# FPGA_FMC.net
KiCad netlist of a schematic drawn in Altium Designer
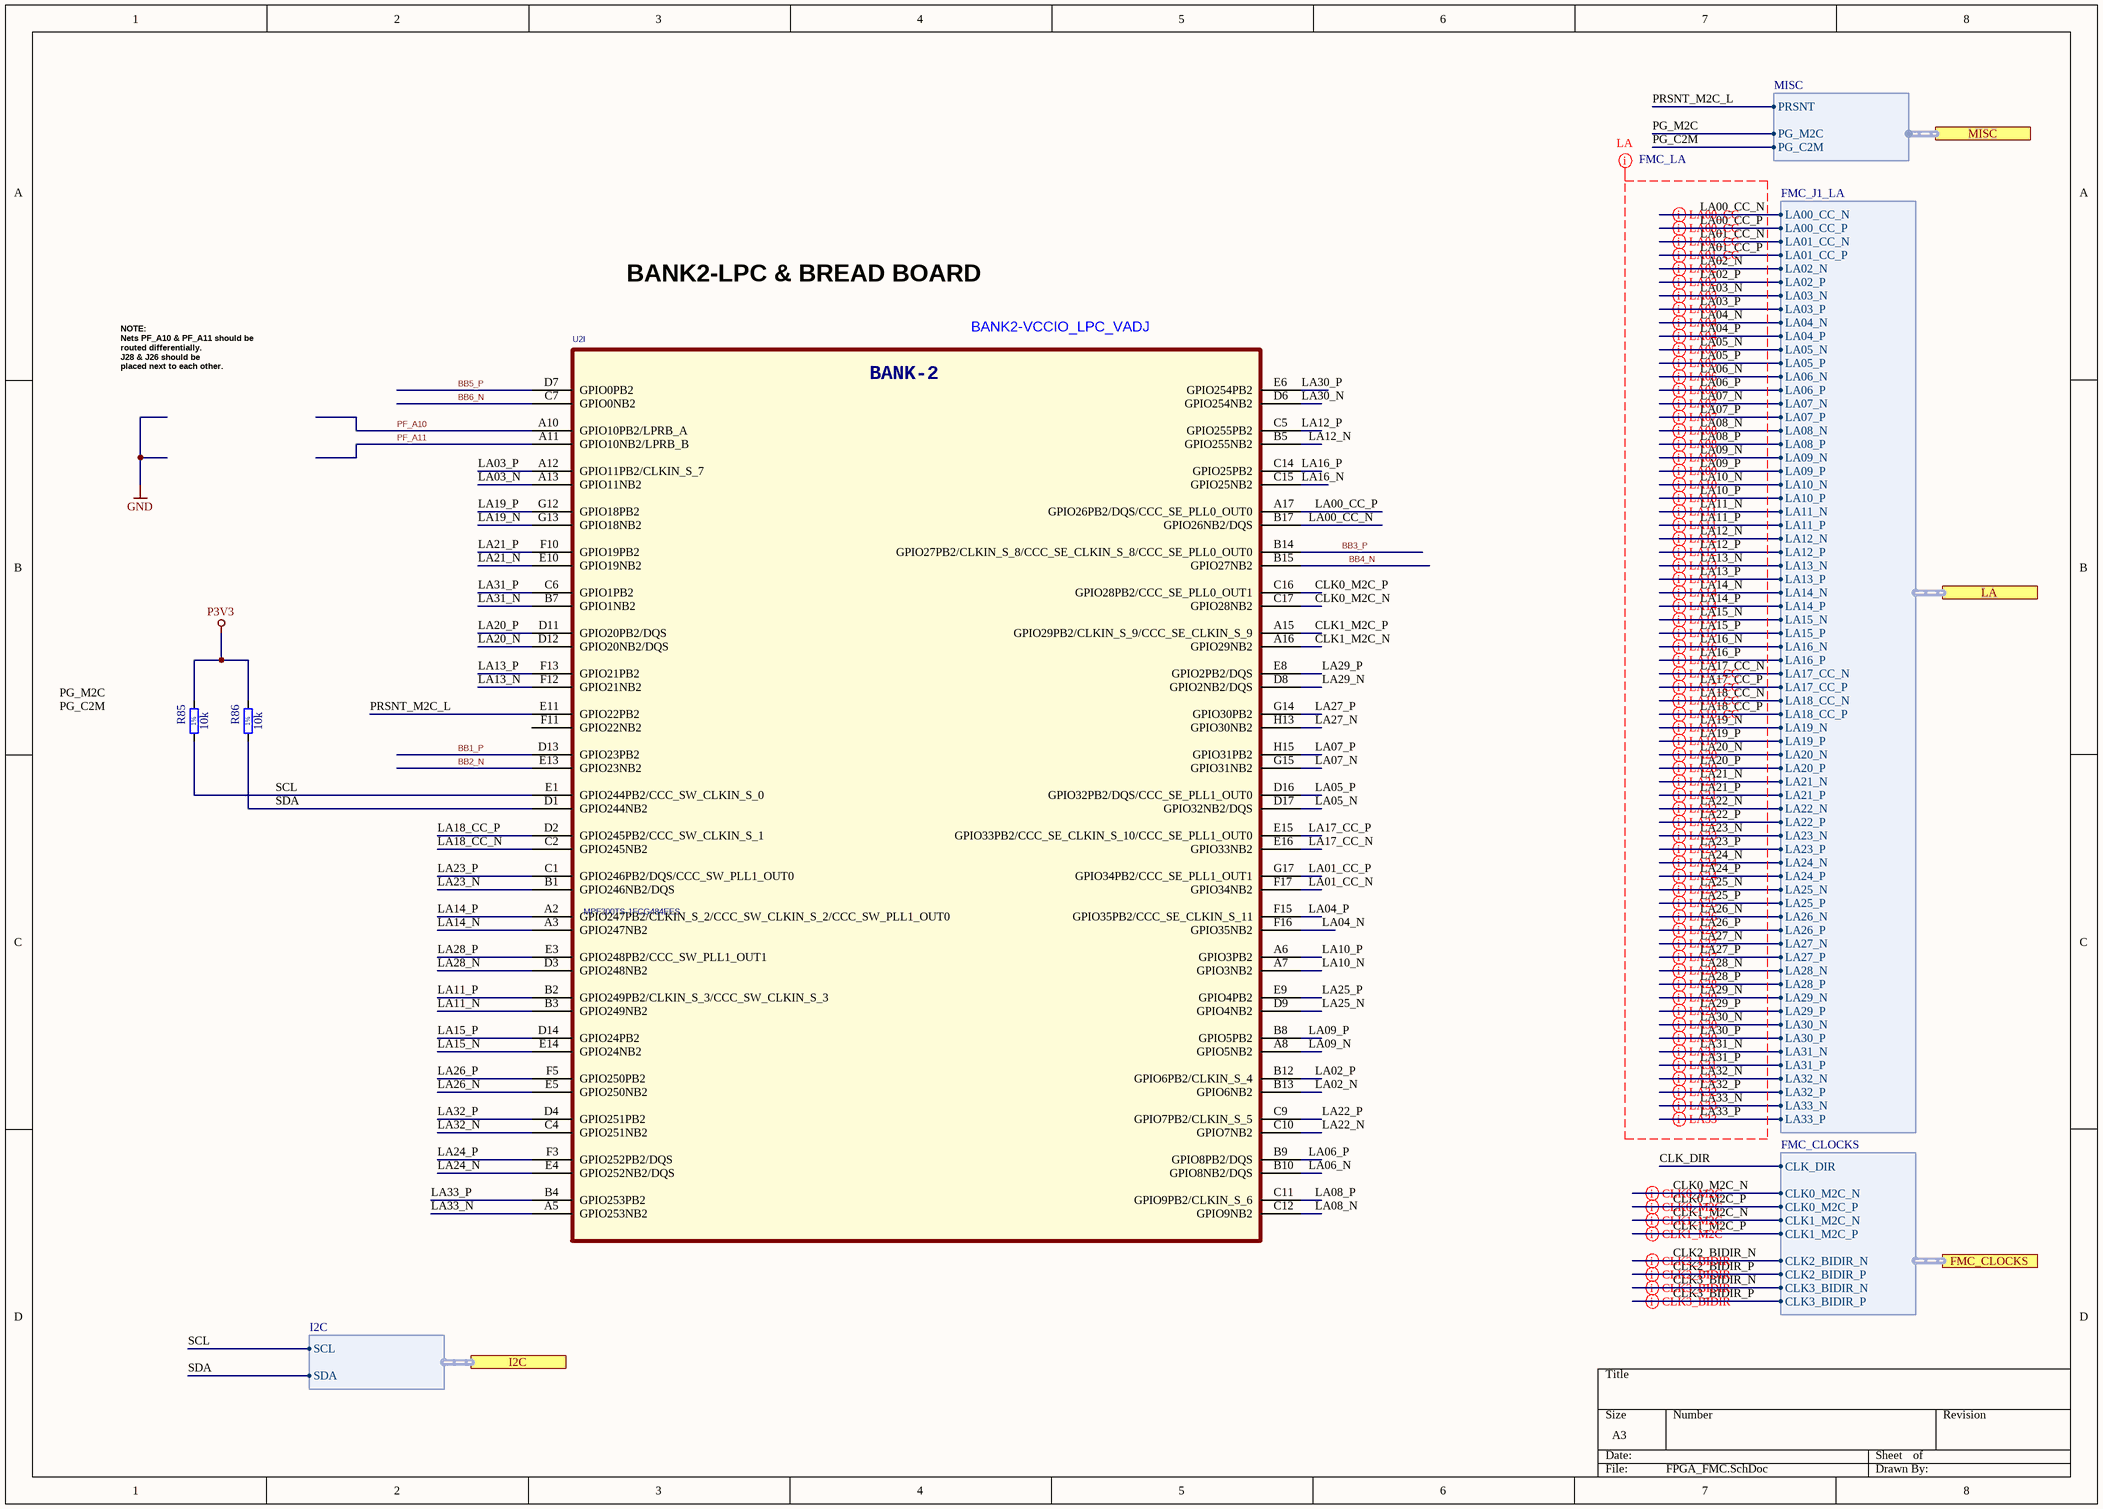
[diagram p0: FPGA_FMC.SchDoc]

(export (version "E")
  (design (tool "Eeschema 10.0.6"))
  (components
    (comp (ref "R85")
      (value "10k")
      (footprint "RESC1005X40N")
      (description "Resistor - 1%")
      (fields
        (field (name "MANUFACTURER PART NUMBER") "R0402_10K_1%_0.0625W_100PPM")
        (field (name "MANUFACTURER") "GENERIC")
        (field (name "AUTHOR") "CERN DEM JLC")
      )
      (libsource (lib "Resistors") (part "Resistor - 1%"))
    )
    (comp (ref "R86")
      (value "10k")
      (footprint "RESC1005X40N")
      (description "Resistor - 1%")
      (fields
        (field (name "MANUFACTURER PART NUMBER") "R0402_10K_1%_0.0625W_100PPM")
        (field (name "MANUFACTURER") "GENERIC")
        (field (name "AUTHOR") "CERN DEM JLC")
      )
      (libsource (lib "Resistors") (part "Resistor - 1%"))
    )
    (comp (ref "U2")
      (value "MPF300TS-1FCG484EES")
      (footprint "BGA484C100P22X22_2300X2300X320")
      (description "FCG484,23mmX23mm,1.0mm pitch")
      (fields (field (name "MANUFACTURER") "Microsemi") (field (name "PART NUMBER") "MPF300TS-1FCG484I"))
      (libsource (lib "LIBRARY_SCH") (part "FPGA_MPF300T-FCG484"))
    )
  )
  (nets
    (net (code "5") (name "/BB1_P") (class "Default")
      (node (ref "U2") (pin "D13") (pinfunction "GPIO23PB2_D13") (pintype "passive"))
    )
    (net (code "6") (name "/BB2_N") (class "Default")
      (node (ref "U2") (pin "E13") (pinfunction "GPIO23NB2_E13") (pintype "passive"))
    )
    (net (code "7") (name "/BB3_P") (class "Default")
      (node (ref "U2") (pin "B14") (pinfunction "GPIO27PB2/CLKIN_S_8/CCC_SE_CLKIN_S_8/CCC_SE_PLL0_OUT0_B14") (pintype "passive"))
    )
    (net (code "8") (name "/BB4_N") (class "Default")
      (node (ref "U2") (pin "B15") (pinfunction "GPIO27NB2_B15") (pintype "passive"))
    )
    (net (code "9") (name "/BB5_P") (class "Default")
      (node (ref "U2") (pin "D7") (pinfunction "GPIO0PB2_D7") (pintype "passive"))
    )
    (net (code "10") (name "/BB6_N") (class "Default")
      (node (ref "U2") (pin "C7") (pinfunction "GPIO0NB2_C7") (pintype "passive"))
    )
    (net (code "11") (name "/CLK0_M2C_N") (class "Default")
      (node (ref "U2") (pin "C17") (pinfunction "GPIO28NB2_C17") (pintype "passive"))
    )
    (net (code "12") (name "/CLK0_M2C_P") (class "Default")
      (node (ref "U2") (pin "C16") (pinfunction "GPIO28PB2/CCC_SE_PLL0_OUT1_C16") (pintype "passive"))
    )
    (net (code "13") (name "/CLK1_M2C_N") (class "Default")
      (node (ref "U2") (pin "A16") (pinfunction "GPIO29NB2_A16") (pintype "passive"))
    )
    (net (code "14") (name "/CLK1_M2C_P") (class "Default")
      (node (ref "U2") (pin "A15") (pinfunction "GPIO29PB2/CLKIN_S_9/CCC_SE_CLKIN_S_9_A15") (pintype "passive"))
    )
    (net (code "20") (name "/LA00_CC_N") (class "Default")
      (node (ref "U2") (pin "B17") (pinfunction "GPIO26NB2/DQS_B17") (pintype "passive"))
    )
    (net (code "21") (name "/LA00_CC_P") (class "Default")
      (node (ref "U2") (pin "A17") (pinfunction "GPIO26PB2/DQS/CCC_SE_PLL0_OUT0_A17") (pintype "passive"))
    )
    (net (code "22") (name "/LA01_CC_N") (class "Default")
      (node (ref "U2") (pin "F17") (pinfunction "GPIO34NB2_F17") (pintype "passive"))
    )
    (net (code "23") (name "/LA01_CC_P") (class "Default")
      (node (ref "U2") (pin "G17") (pinfunction "GPIO34PB2/CCC_SE_PLL1_OUT1_G17") (pintype "passive"))
    )
    (net (code "24") (name "/LA02_N") (class "Default")
      (node (ref "U2") (pin "B13") (pinfunction "GPIO6NB2_B13") (pintype "passive"))
    )
    (net (code "25") (name "/LA02_P") (class "Default")
      (node (ref "U2") (pin "B12") (pinfunction "GPIO6PB2/CLKIN_S_4_B12") (pintype "passive"))
    )
    (net (code "26") (name "/LA03_N") (class "Default")
      (node (ref "U2") (pin "A13") (pinfunction "GPIO11NB2_A13") (pintype "passive"))
    )
    (net (code "27") (name "/LA03_P") (class "Default")
      (node (ref "U2") (pin "A12") (pinfunction "GPIO11PB2/CLKIN_S_7_A12") (pintype "passive"))
    )
    (net (code "28") (name "/LA04_N") (class "Default")
      (node (ref "U2") (pin "F16") (pinfunction "GPIO35NB2_F16") (pintype "passive"))
    )
    (net (code "29") (name "/LA04_P") (class "Default")
      (node (ref "U2") (pin "F15") (pinfunction "GPIO35PB2/CCC_SE_CLKIN_S_11_F15") (pintype "passive"))
    )
    (net (code "30") (name "/LA05_N") (class "Default")
      (node (ref "U2") (pin "D17") (pinfunction "GPIO32NB2/DQS_D17") (pintype "passive"))
    )
    (net (code "31") (name "/LA05_P") (class "Default")
      (node (ref "U2") (pin "D16") (pinfunction "GPIO32PB2/DQS/CCC_SE_PLL1_OUT0_D16") (pintype "passive"))
    )
    (net (code "32") (name "/LA06_N") (class "Default")
      (node (ref "U2") (pin "B10") (pinfunction "GPIO8NB2/DQS_B10") (pintype "passive"))
    )
    (net (code "33") (name "/LA06_P") (class "Default")
      (node (ref "U2") (pin "B9") (pinfunction "GPIO8PB2/DQS_B9") (pintype "passive"))
    )
    (net (code "34") (name "/LA07_N") (class "Default")
      (node (ref "U2") (pin "G15") (pinfunction "GPIO31NB2_G15") (pintype "passive"))
    )
    (net (code "35") (name "/LA07_P") (class "Default")
      (node (ref "U2") (pin "H15") (pinfunction "GPIO31PB2_H15") (pintype "passive"))
    )
    (net (code "36") (name "/LA08_N") (class "Default")
      (node (ref "U2") (pin "C12") (pinfunction "GPIO9NB2_C12") (pintype "passive"))
    )
    (net (code "37") (name "/LA08_P") (class "Default")
      (node (ref "U2") (pin "C11") (pinfunction "GPIO9PB2/CLKIN_S_6_C11") (pintype "passive"))
    )
    (net (code "38") (name "/LA09_N") (class "Default")
      (node (ref "U2") (pin "A8") (pinfunction "GPIO5NB2_A8") (pintype "passive"))
    )
    (net (code "39") (name "/LA09_P") (class "Default")
      (node (ref "U2") (pin "B8") (pinfunction "GPIO5PB2_B8") (pintype "passive"))
    )
    (net (code "40") (name "/LA10_N") (class "Default")
      (node (ref "U2") (pin "A7") (pinfunction "GPIO3NB2_A7") (pintype "passive"))
    )
    (net (code "41") (name "/LA10_P") (class "Default")
      (node (ref "U2") (pin "A6") (pinfunction "GPIO3PB2_A6") (pintype "passive"))
    )
    (net (code "42") (name "/LA11_N") (class "Default")
      (node (ref "U2") (pin "B3") (pinfunction "GPIO249NB2_B3") (pintype "passive"))
    )
    (net (code "43") (name "/LA11_P") (class "Default")
      (node (ref "U2") (pin "B2") (pinfunction "GPIO249PB2/CLKIN_S_3/CCC_SW_CLKIN_S_3_B2") (pintype "passive"))
    )
    (net (code "44") (name "/LA12_N") (class "Default")
      (node (ref "U2") (pin "B5") (pinfunction "GPIO255NB2_B5") (pintype "passive"))
    )
    (net (code "45") (name "/LA12_P") (class "Default")
      (node (ref "U2") (pin "C5") (pinfunction "GPIO255PB2_C5") (pintype "passive"))
    )
    (net (code "46") (name "/LA13_N") (class "Default")
      (node (ref "U2") (pin "F12") (pinfunction "GPIO21NB2_F12") (pintype "passive"))
    )
    (net (code "47") (name "/LA13_P") (class "Default")
      (node (ref "U2") (pin "F13") (pinfunction "GPIO21PB2_F13") (pintype "passive"))
    )
    (net (code "48") (name "/LA14_N") (class "Default")
      (node (ref "U2") (pin "A3") (pinfunction "GPIO247NB2_A3") (pintype "passive"))
    )
    (net (code "49") (name "/LA14_P") (class "Default")
      (node (ref "U2") (pin "A2") (pinfunction "GPIO247PB2/CLKIN_S_2/CCC_SW_CLKIN_S_2/CCC_SW_PLL1_OUT0_A2") (pintype "passive"))
    )
    (net (code "50") (name "/LA15_N") (class "Default")
      (node (ref "U2") (pin "E14") (pinfunction "GPIO24NB2_E14") (pintype "passive"))
    )
    (net (code "51") (name "/LA15_P") (class "Default")
      (node (ref "U2") (pin "D14") (pinfunction "GPIO24PB2_D14") (pintype "passive"))
    )
    (net (code "52") (name "/LA16_N") (class "Default")
      (node (ref "U2") (pin "C15") (pinfunction "GPIO25NB2_C15") (pintype "passive"))
    )
    (net (code "53") (name "/LA16_P") (class "Default")
      (node (ref "U2") (pin "C14") (pinfunction "GPIO25PB2_C14") (pintype "passive"))
    )
    (net (code "54") (name "/LA17_CC_N") (class "Default")
      (node (ref "U2") (pin "E16") (pinfunction "GPIO33NB2_E16") (pintype "passive"))
    )
    (net (code "55") (name "/LA17_CC_P") (class "Default")
      (node (ref "U2") (pin "E15") (pinfunction "GPIO33PB2/CCC_SE_CLKIN_S_10/CCC_SE_PLL1_OUT0_E15") (pintype "passive"))
    )
    (net (code "56") (name "/LA18_CC_N") (class "Default")
      (node (ref "U2") (pin "C2") (pinfunction "GPIO245NB2_C2") (pintype "passive"))
    )
    (net (code "57") (name "/LA18_CC_P") (class "Default")
      (node (ref "U2") (pin "D2") (pinfunction "GPIO245PB2/CCC_SW_CLKIN_S_1_D2") (pintype "passive"))
    )
    (net (code "58") (name "/LA19_N") (class "Default")
      (node (ref "U2") (pin "G13") (pinfunction "GPIO18NB2_G13") (pintype "passive"))
    )
    (net (code "59") (name "/LA19_P") (class "Default")
      (node (ref "U2") (pin "G12") (pinfunction "GPIO18PB2_G12") (pintype "passive"))
    )
    (net (code "60") (name "/LA20_N") (class "Default")
      (node (ref "U2") (pin "D12") (pinfunction "GPIO20NB2/DQS_D12") (pintype "passive"))
    )
    (net (code "61") (name "/LA20_P") (class "Default")
      (node (ref "U2") (pin "D11") (pinfunction "GPIO20PB2/DQS_D11") (pintype "passive"))
    )
    (net (code "62") (name "/LA21_N") (class "Default")
      (node (ref "U2") (pin "E10") (pinfunction "GPIO19NB2_E10") (pintype "passive"))
    )
    (net (code "63") (name "/LA21_P") (class "Default")
      (node (ref "U2") (pin "F10") (pinfunction "GPIO19PB2_F10") (pintype "passive"))
    )
    (net (code "64") (name "/LA22_N") (class "Default")
      (node (ref "U2") (pin "C10") (pinfunction "GPIO7NB2_C10") (pintype "passive"))
    )
    (net (code "65") (name "/LA22_P") (class "Default")
      (node (ref "U2") (pin "C9") (pinfunction "GPIO7PB2/CLKIN_S_5_C9") (pintype "passive"))
    )
    (net (code "66") (name "/LA23_N") (class "Default")
      (node (ref "U2") (pin "B1") (pinfunction "GPIO246NB2/DQS_B1") (pintype "passive"))
    )
    (net (code "67") (name "/LA23_P") (class "Default")
      (node (ref "U2") (pin "C1") (pinfunction "GPIO246PB2/DQS/CCC_SW_PLL1_OUT0_C1") (pintype "passive"))
    )
    (net (code "68") (name "/LA24_N") (class "Default")
      (node (ref "U2") (pin "E4") (pinfunction "GPIO252NB2/DQS_E4") (pintype "passive"))
    )
    (net (code "69") (name "/LA24_P") (class "Default")
      (node (ref "U2") (pin "F3") (pinfunction "GPIO252PB2/DQS_F3") (pintype "passive"))
    )
    (net (code "70") (name "/LA25_N") (class "Default")
      (node (ref "U2") (pin "D9") (pinfunction "GPIO4NB2_D9") (pintype "passive"))
    )
    (net (code "71") (name "/LA25_P") (class "Default")
      (node (ref "U2") (pin "E9") (pinfunction "GPIO4PB2_E9") (pintype "passive"))
    )
    (net (code "72") (name "/LA26_N") (class "Default")
      (node (ref "U2") (pin "E5") (pinfunction "GPIO250NB2_E5") (pintype "passive"))
    )
    (net (code "73") (name "/LA26_P") (class "Default")
      (node (ref "U2") (pin "F5") (pinfunction "GPIO250PB2_F5") (pintype "passive"))
    )
    (net (code "74") (name "/LA27_N") (class "Default")
      (node (ref "U2") (pin "H13") (pinfunction "GPIO30NB2_H13") (pintype "passive"))
    )
    (net (code "75") (name "/LA27_P") (class "Default")
      (node (ref "U2") (pin "G14") (pinfunction "GPIO30PB2_G14") (pintype "passive"))
    )
    (net (code "76") (name "/LA28_N") (class "Default")
      (node (ref "U2") (pin "D3") (pinfunction "GPIO248NB2_D3") (pintype "passive"))
    )
    (net (code "77") (name "/LA28_P") (class "Default")
      (node (ref "U2") (pin "E3") (pinfunction "GPIO248PB2/CCC_SW_PLL1_OUT1_E3") (pintype "passive"))
    )
    (net (code "78") (name "/LA29_N") (class "Default")
      (node (ref "U2") (pin "D8") (pinfunction "GPIO2NB2/DQS_D8") (pintype "passive"))
    )
    (net (code "79") (name "/LA29_P") (class "Default")
      (node (ref "U2") (pin "E8") (pinfunction "GPIO2PB2/DQS_E8") (pintype "passive"))
    )
    (net (code "80") (name "/LA30_N") (class "Default")
      (node (ref "U2") (pin "D6") (pinfunction "GPIO254NB2_D6") (pintype "passive"))
    )
    (net (code "81") (name "/LA30_P") (class "Default")
      (node (ref "U2") (pin "E6") (pinfunction "GPIO254PB2_E6") (pintype "passive"))
    )
    (net (code "82") (name "/LA31_N") (class "Default")
      (node (ref "U2") (pin "B7") (pinfunction "GPIO1NB2_B7") (pintype "passive"))
    )
    (net (code "83") (name "/LA31_P") (class "Default")
      (node (ref "U2") (pin "C6") (pinfunction "GPIO1PB2_C6") (pintype "passive"))
    )
    (net (code "84") (name "/LA32_N") (class "Default")
      (node (ref "U2") (pin "C4") (pinfunction "GPIO251NB2_C4") (pintype "passive"))
    )
    (net (code "85") (name "/LA32_P") (class "Default")
      (node (ref "U2") (pin "D4") (pinfunction "GPIO251PB2_D4") (pintype "passive"))
    )
    (net (code "86") (name "/LA33_N") (class "Default")
      (node (ref "U2") (pin "A5") (pinfunction "GPIO253NB2_A5") (pintype "passive"))
    )
    (net (code "87") (name "/LA33_P") (class "Default")
      (node (ref "U2") (pin "B4") (pinfunction "GPIO253PB2_B4") (pintype "passive"))
    )
    (net (code "88") (name "/PF_A10") (class "Default")
      (node (ref "U2") (pin "A10") (pinfunction "GPIO10PB2/LPRB_A_A10") (pintype "passive"))
    )
    (net (code "89") (name "/PF_A11") (class "Default")
      (node (ref "U2") (pin "A11") (pinfunction "GPIO10NB2/LPRB_B_A11") (pintype "passive"))
    )
    (net (code "92") (name "/PRSNT_M2C_L") (class "Default")
      (node (ref "U2") (pin "E11") (pinfunction "GPIO22PB2_E11") (pintype "passive"))
    )
    (net (code "93") (name "/SCL") (class "Default")
      (node (ref "R85") (pin "1") (pinfunction "1_1") (pintype "passive"))
      (node (ref "U2") (pin "E1") (pinfunction "GPIO244PB2/CCC_SW_CLKIN_S_0_E1") (pintype "passive"))
    )
    (net (code "94") (name "/SDA") (class "Default")
      (node (ref "R86") (pin "1") (pinfunction "1_1") (pintype "passive"))
      (node (ref "U2") (pin "D1") (pinfunction "GPIO244NB2_D1") (pintype "passive"))
    )
    (net (code "100") (name "P3V3") (class "Default")
      (node (ref "R85") (pin "2") (pinfunction "2_2") (pintype "passive"))
      (node (ref "R86") (pin "2") (pinfunction "2_2") (pintype "passive"))
    )
    (net (code "101") (name "unconnected-(U2I-GPIO22NB2-PadF11)") (class "Default")
      (node (ref "U2") (pin "F11") (pinfunction "GPIO22NB2_F11") (pintype "passive"))
    )
  )
)
